# rot-brace.net
KiCad netlist of a schematic drawn in EAGLE
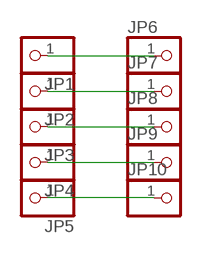
[diagram p0: schematic, sheet 1]

(export (version "E")
  (design (tool "Eeschema 10.0.6"))
  (components
    (comp (ref "JP1")
      (value "HEADER-1X1ROUND")
      (footprint "eagle-import:1X01_ROUND")
      (libsource (lib "eagle-import") (part "HEADER-1X1ROUND"))
    )
    (comp (ref "JP2")
      (value "HEADER-1X1ROUND")
      (footprint "eagle-import:1X01_ROUND")
      (libsource (lib "eagle-import") (part "HEADER-1X1ROUND"))
    )
    (comp (ref "JP3")
      (value "HEADER-1X1ROUND")
      (footprint "eagle-import:1X01_ROUND")
      (libsource (lib "eagle-import") (part "HEADER-1X1ROUND"))
    )
    (comp (ref "JP4")
      (value "HEADER-1X1ROUND")
      (footprint "eagle-import:1X01_ROUND")
      (libsource (lib "eagle-import") (part "HEADER-1X1ROUND"))
    )
    (comp (ref "JP5")
      (value "HEADER-1X1ROUND")
      (footprint "eagle-import:1X01_ROUND")
      (libsource (lib "eagle-import") (part "HEADER-1X1ROUND"))
    )
    (comp (ref "JP6")
      (value "HEADER-1X1ROUND")
      (footprint "eagle-import:1X01_ROUND")
      (libsource (lib "eagle-import") (part "HEADER-1X1ROUND"))
    )
    (comp (ref "JP7")
      (value "HEADER-1X1ROUND")
      (footprint "eagle-import:1X01_ROUND")
      (libsource (lib "eagle-import") (part "HEADER-1X1ROUND"))
    )
    (comp (ref "JP8")
      (value "HEADER-1X1ROUND")
      (footprint "eagle-import:1X01_ROUND")
      (libsource (lib "eagle-import") (part "HEADER-1X1ROUND"))
    )
    (comp (ref "JP9")
      (value "HEADER-1X1ROUND")
      (footprint "eagle-import:1X01_ROUND")
      (libsource (lib "eagle-import") (part "HEADER-1X1ROUND"))
    )
    (comp (ref "JP10")
      (value "HEADER-1X1ROUND")
      (footprint "eagle-import:1X01_ROUND")
      (libsource (lib "eagle-import") (part "HEADER-1X1ROUND"))
    )
  )
  (nets
    (net (code "1") (name "Net-(JP1-Pad1)") (class "Default")
      (node (ref "JP1") (pin "1") (pinfunction "1_1") (pintype "passive"))
      (node (ref "JP6") (pin "1") (pinfunction "1_1") (pintype "passive"))
    )
    (net (code "2") (name "Net-(JP2-Pad1)") (class "Default")
      (node (ref "JP2") (pin "1") (pinfunction "1_1") (pintype "passive"))
      (node (ref "JP7") (pin "1") (pinfunction "1_1") (pintype "passive"))
    )
    (net (code "3") (name "Net-(JP3-Pad1)") (class "Default")
      (node (ref "JP3") (pin "1") (pinfunction "1_1") (pintype "passive"))
      (node (ref "JP8") (pin "1") (pinfunction "1_1") (pintype "passive"))
    )
    (net (code "4") (name "Net-(JP4-Pad1)") (class "Default")
      (node (ref "JP4") (pin "1") (pinfunction "1_1") (pintype "passive"))
      (node (ref "JP9") (pin "1") (pinfunction "1_1") (pintype "passive"))
    )
    (net (code "5") (name "Net-(JP10-Pad1)") (class "Default")
      (node (ref "JP10") (pin "1") (pinfunction "1_1") (pintype "passive"))
      (node (ref "JP5") (pin "1") (pinfunction "1_1") (pintype "passive"))
    )
  )
)
